# Tp_7seg.net
KiCad netlist of a schematic drawn in Altium Designer
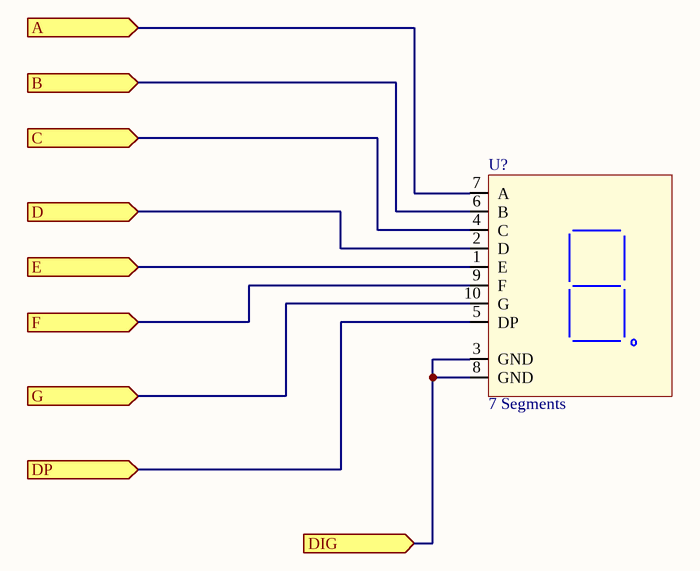
[diagram p0: Tp_7seg.SchDoc]

(export (version "E")
  (design (tool "Eeschema 10.0.6"))
  (components
    (comp (ref "U?")
      (value "7 Segments")
      (footprint "SA10-21GWA")
      (description "KingBright Led 7 Segments")
      (libsource (lib "TpGiven") (part "SC10-21SRWA"))
    )
  )
  (nets
    (net (code "1") (name "/A") (class "Default")
      (node (ref "U?") (pin "7") (pinfunction "A_7") (pintype "passive"))
    )
    (net (code "2") (name "/B") (class "Default")
      (node (ref "U?") (pin "6") (pinfunction "B_6") (pintype "passive"))
    )
    (net (code "3") (name "/C") (class "Default")
      (node (ref "U?") (pin "4") (pinfunction "C_4") (pintype "passive"))
    )
    (net (code "4") (name "/D") (class "Default")
      (node (ref "U?") (pin "2") (pinfunction "D_2") (pintype "passive"))
    )
    (net (code "5") (name "/DIG") (class "Default")
      (node (ref "U?") (pin "3") (pinfunction "GND_3") (pintype "passive"))
      (node (ref "U?") (pin "8") (pinfunction "GND_8") (pintype "passive"))
    )
    (net (code "6") (name "/DP") (class "Default")
      (node (ref "U?") (pin "5") (pinfunction "DP_5") (pintype "passive"))
    )
    (net (code "7") (name "/E") (class "Default")
      (node (ref "U?") (pin "1") (pinfunction "E_1") (pintype "passive"))
    )
    (net (code "8") (name "/F") (class "Default")
      (node (ref "U?") (pin "9") (pinfunction "F_9") (pintype "passive"))
    )
    (net (code "9") (name "/G") (class "Default")
      (node (ref "U?") (pin "10") (pinfunction "G_10") (pintype "passive"))
    )
  )
)
